# ESP32_LRThermostat_Relay_Driver_Board.net
KiCad netlist of a schematic drawn in EasyEDA
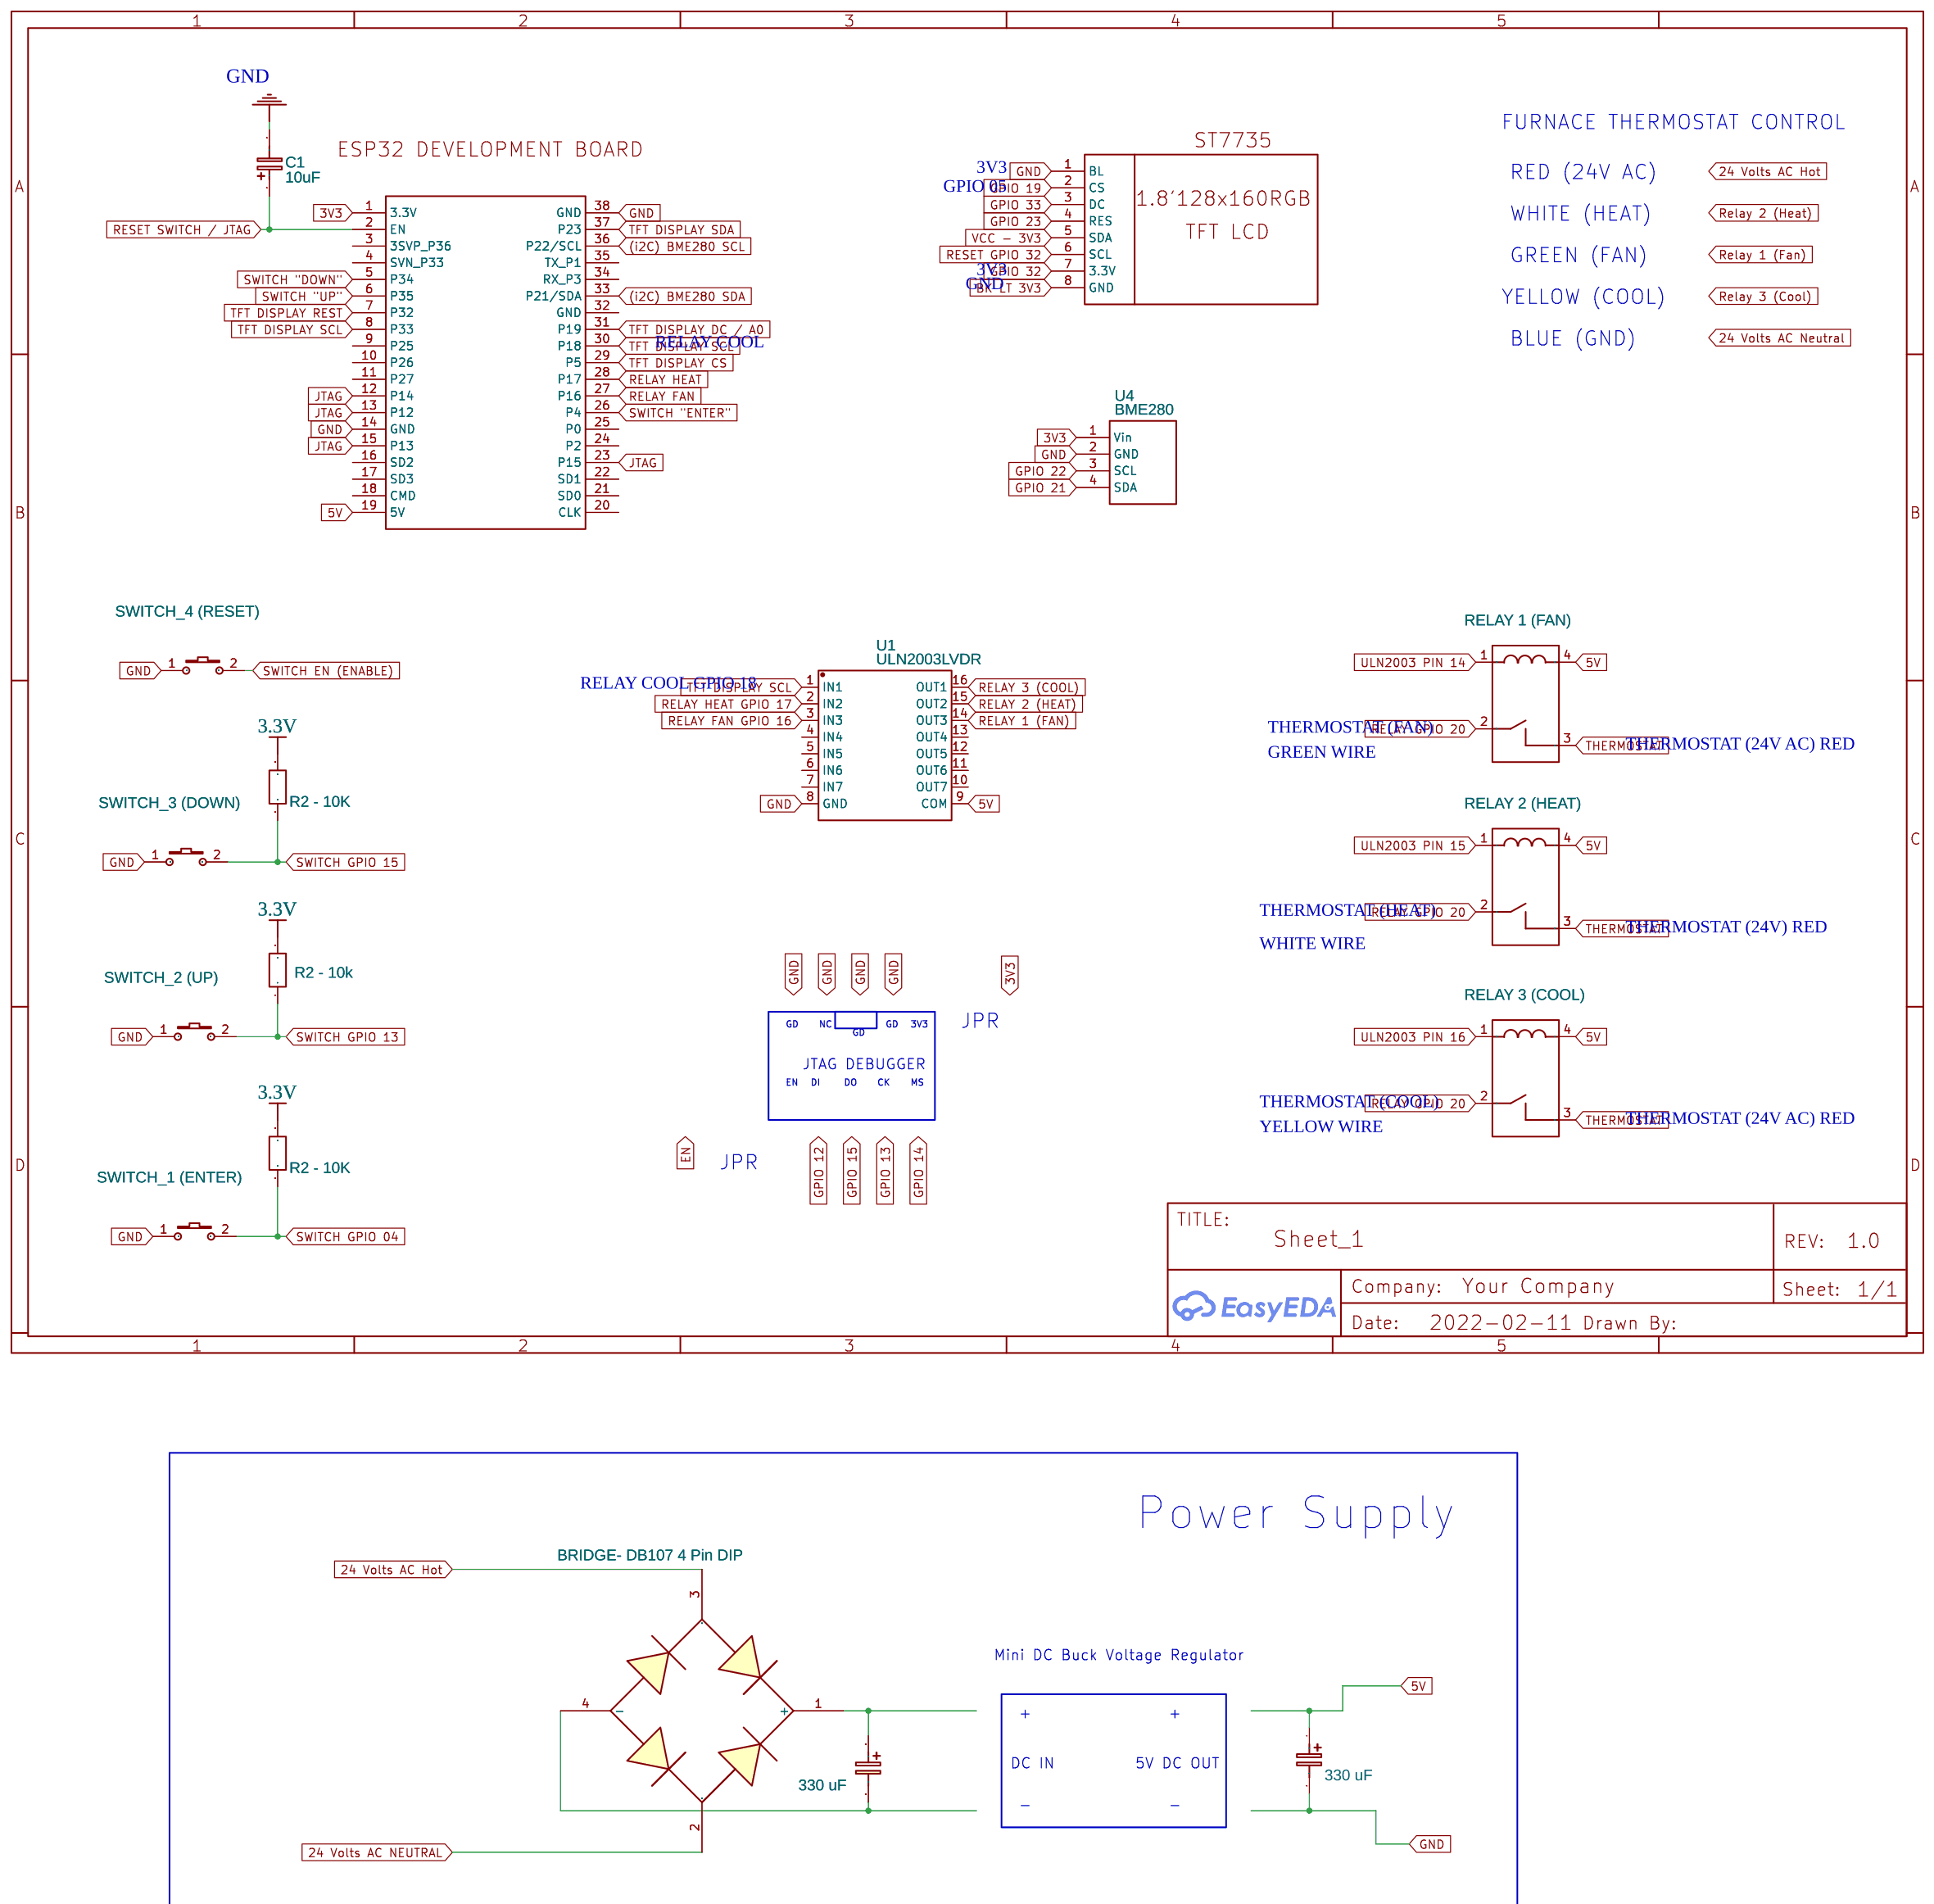
[diagram p0: schematic sheet]

(export (version "E")
  (design (tool "Eeschema 10.0.6"))
  (components
    (comp (ref "C1") (value "10uF") (libsource (lib "") (part "C_Tan_SMD_A_EU")))
    (comp (ref "C2") (value "330 uF") (libsource (lib "") (part "C_Tan_SMD_A_EU_1")))
    (comp (ref "C3") (value "330 uF") (libsource (lib "") (part "C_Tan_SMD_A_EU_1")))
    (comp (ref "D1") (value "BRIDGE- DB107 4 Pin DIP") (libsource (lib "") (part "BRIDGE-1")))
    (comp (ref "K1")
      (value "RELAY 2 (HEAT)")
      (fields
        (field (name "BOM_Manufacturer Part") "RJ-SS-112DM1-S")
        (field (name "BOM_Supplier Part") "C358580")
      )
      (libsource (lib "") (part "RJ-SS-112DM1-S"))
    )
    (comp (ref "K2")
      (value "RELAY 3 (COOL)")
      (fields
        (field (name "BOM_Manufacturer Part") "RJ-SS-112DM1-S")
        (field (name "BOM_Supplier Part") "C358580")
      )
      (libsource (lib "") (part "RJ-SS-112DM1-S"))
    )
    (comp (ref "K4")
      (value "RELAY 1 (FAN)")
      (fields
        (field (name "BOM_Manufacturer Part") "RJ-SS-112DM1-S")
        (field (name "BOM_Supplier Part") "C358580")
      )
      (libsource (lib "") (part "RJ-SS-112DM1-S"))
    )
    (comp (ref "KEY1")
      (value "SWITCH_4 (RESET)")
      (fields
        (field (name "BOM_Manufacturer Part") "K2-1107ST-A4SW-06")
        (field (name "BOM_Supplier Part") "C118141")
      )
      (libsource (lib "") (part "K2-3.6×6.1_SMD"))
    )
    (comp (ref "KEY4")
      (value "SWITCH_3 (DOWN)")
      (fields
        (field (name "BOM_Manufacturer Part") "K2-1107ST-A4SW-06")
        (field (name "BOM_Supplier Part") "C118141")
      )
      (libsource (lib "") (part "K2-3.6×6.1_SMD"))
    )
    (comp (ref "KEY5")
      (value "SWITCH_1 (ENTER)")
      (fields
        (field (name "BOM_Manufacturer Part") "K2-1107ST-A4SW-06")
        (field (name "BOM_Supplier Part") "C118141")
      )
      (libsource (lib "") (part "K2-3.6×6.1_SMD"))
    )
    (comp (ref "KEY6")
      (value "SWITCH_2 (UP)")
      (fields
        (field (name "BOM_Manufacturer Part") "K2-1107ST-A4SW-06")
        (field (name "BOM_Supplier Part") "C118141")
      )
      (libsource (lib "") (part "K2-3.6×6.1_SMD"))
    )
    (comp (ref "R1") (value "R2 - 10k") (libsource (lib "") (part "R_0603_EU")))
    (comp (ref "R2") (value "R2 - 10K") (libsource (lib "") (part "R_0603_EU")))
    (comp (ref "R3") (value "R2 - 10K") (libsource (lib "") (part "R_0603_EU")))
    (comp (ref "U1")
      (value "ULN2003LVDR")
      (fields (field (name "BOM_Supplier Part") "C72751"))
      (libsource (lib "") (part "ULN2003LVDR"))
    )
    (comp (ref "U2")
      (value "ESP32S Devkit")
      (fields (field (name "BOM_Manufacturer Part") "New SchematicLib"))
      (libsource (lib "") (part "ESP32S Devkit"))
    )
    (comp (ref "U3") (value "ST7735") (libsource (lib "") (part "ST7735")))
    (comp (ref "U4") (value "BME280") (libsource (lib "") (part "BME280")))
  )
  (nets
    (net (code "1") (name "(i2C) BME280 SCL") (class "Default")
      (node (ref "U2") (pin "36") (pinfunction "P22/SCL_36") (pintype "unspecified"))
    )
    (net (code "2") (name "(i2C) BME280 SDA") (class "Default")
      (node (ref "U2") (pin "33") (pinfunction "P21/SDA_33") (pintype "unspecified"))
    )
    (net (code "3") (name "3.3V") (class "Default")
      (node (ref "R1") (pin "2") (pinfunction "2_2") (pintype "unspecified"))
      (node (ref "R2") (pin "2") (pinfunction "2_2") (pintype "unspecified"))
      (node (ref "R3") (pin "2") (pinfunction "2_2") (pintype "unspecified"))
    )
    (net (code "4") (name "3V3") (class "Default")
      (node (ref "U2") (pin "1") (pinfunction "3.3V_1") (pintype "unspecified"))
      (node (ref "U4") (pin "1") (pinfunction "Vin_1") (pintype "unspecified"))
    )
    (net (code "5") (name "5V") (class "Default")
      (node (ref "C3") (pin "1") (pinfunction "1_1") (pintype "unspecified"))
      (node (ref "K1") (pin "4") (pinfunction "4_4") (pintype "unspecified"))
      (node (ref "K2") (pin "4") (pinfunction "4_4") (pintype "unspecified"))
      (node (ref "K4") (pin "4") (pinfunction "4_4") (pintype "unspecified"))
      (node (ref "U1") (pin "9") (pinfunction "COM_9") (pintype "unspecified"))
      (node (ref "U2") (pin "19") (pinfunction "5V_19") (pintype "unspecified"))
    )
    (net (code "6") (name "24 Volts AC Hot") (class "Default")
      (node (ref "D1") (pin "3") (pinfunction "3_3") (pintype "input"))
    )
    (net (code "7") (name "24 Volts AC NEUTRAL") (class "Default")
      (node (ref "D1") (pin "2") (pinfunction "2_2") (pintype "input"))
    )
    (net (code "9") (name "BK LT 3V3") (class "Default")
      (node (ref "U3") (pin "8") (pinfunction "GND_8") (pintype "unspecified"))
    )
    (net (code "11") (name "GND") (class "Default")
      (node (ref "C1") (pin "2") (pinfunction "2_2") (pintype "unspecified"))
      (node (ref "C3") (pin "2") (pinfunction "2_2") (pintype "unspecified"))
      (node (ref "KEY1") (pin "1") (pinfunction "1_1") (pintype "unspecified"))
      (node (ref "KEY4") (pin "1") (pinfunction "1_1") (pintype "unspecified"))
      (node (ref "KEY5") (pin "1") (pinfunction "1_1") (pintype "unspecified"))
      (node (ref "KEY6") (pin "1") (pinfunction "1_1") (pintype "unspecified"))
      (node (ref "U1") (pin "8") (pinfunction "GND_8") (pintype "unspecified"))
      (node (ref "U2") (pin "14") (pinfunction "GND_14") (pintype "unspecified"))
      (node (ref "U2") (pin "38") (pinfunction "GND_38") (pintype "unspecified"))
      (node (ref "U3") (pin "1") (pinfunction "BL_1") (pintype "unspecified"))
      (node (ref "U4") (pin "2") (pinfunction "GND_2") (pintype "unspecified"))
    )
    (net (code "16") (name "GPIO 19") (class "Default")
      (node (ref "U3") (pin "2") (pinfunction "CS_2") (pintype "unspecified"))
    )
    (net (code "17") (name "GPIO 21") (class "Default")
      (node (ref "U4") (pin "4") (pinfunction "SDA_4") (pintype "unspecified"))
    )
    (net (code "18") (name "GPIO 22") (class "Default")
      (node (ref "U4") (pin "3") (pinfunction "SCL_3") (pintype "unspecified"))
    )
    (net (code "19") (name "GPIO 23") (class "Default")
      (node (ref "U3") (pin "4") (pinfunction "RES_4") (pintype "unspecified"))
    )
    (net (code "20") (name "GPIO 32") (class "Default")
      (node (ref "U3") (pin "7") (pinfunction "3.3V_7") (pintype "unspecified"))
    )
    (net (code "21") (name "GPIO 33") (class "Default")
      (node (ref "U3") (pin "3") (pinfunction "DC_3") (pintype "unspecified"))
    )
    (net (code "22") (name "JTAG") (class "Default")
      (node (ref "U2") (pin "12") (pinfunction "P14_12") (pintype "unspecified"))
      (node (ref "U2") (pin "13") (pinfunction "P12_13") (pintype "unspecified"))
      (node (ref "U2") (pin "15") (pinfunction "P13_15") (pintype "unspecified"))
      (node (ref "U2") (pin "23") (pinfunction "P15_23") (pintype "unspecified"))
    )
    (net (code "23") (name "Net-(D1-+)") (class "Default")
      (node (ref "C2") (pin "1") (pinfunction "1_1") (pintype "unspecified"))
      (node (ref "D1") (pin "1") (pinfunction "+_1") (pintype "input"))
    )
    (net (code "24") (name "Net-(D1--)") (class "Default")
      (node (ref "C2") (pin "2") (pinfunction "2_2") (pintype "unspecified"))
      (node (ref "D1") (pin "4") (pinfunction "-_4") (pintype "input"))
    )
    (net (code "25") (name "RELAY 1 (FAN)") (class "Default")
      (node (ref "U1") (pin "14") (pinfunction "OUT3_14") (pintype "unspecified"))
    )
    (net (code "26") (name "RELAY 2 (HEAT)") (class "Default")
      (node (ref "U1") (pin "15") (pinfunction "OUT2_15") (pintype "unspecified"))
    )
    (net (code "27") (name "RELAY 3 (COOL)") (class "Default")
      (node (ref "U1") (pin "16") (pinfunction "OUT1_16") (pintype "unspecified"))
    )
    (net (code "28") (name "RELAY FAN") (class "Default")
      (node (ref "U2") (pin "27") (pinfunction "P16_27") (pintype "unspecified"))
    )
    (net (code "29") (name "RELAY FAN GPIO 16") (class "Default")
      (node (ref "U1") (pin "3") (pinfunction "IN3_3") (pintype "unspecified"))
    )
    (net (code "30") (name "RELAY GPIO 20") (class "Default")
      (node (ref "K1") (pin "2") (pinfunction "2_2") (pintype "unspecified"))
      (node (ref "K2") (pin "2") (pinfunction "2_2") (pintype "unspecified"))
      (node (ref "K4") (pin "2") (pinfunction "2_2") (pintype "unspecified"))
    )
    (net (code "31") (name "RELAY HEAT") (class "Default")
      (node (ref "U2") (pin "28") (pinfunction "P17_28") (pintype "unspecified"))
    )
    (net (code "32") (name "RELAY HEAT GPIO 17") (class "Default")
      (node (ref "U1") (pin "2") (pinfunction "IN2_2") (pintype "unspecified"))
    )
    (net (code "33") (name "RESET GPIO 32") (class "Default")
      (node (ref "U3") (pin "6") (pinfunction "SCL_6") (pintype "unspecified"))
    )
    (net (code "34") (name "RESET SWITCH {slash} JTAG") (class "Default")
      (node (ref "C1") (pin "1") (pinfunction "1_1") (pintype "unspecified"))
      (node (ref "U2") (pin "2") (pinfunction "EN_2") (pintype "unspecified"))
    )
    (net (code "38") (name "SWITCH \"DOWN\"") (class "Default")
      (node (ref "U2") (pin "5") (pinfunction "P34_5") (pintype "unspecified"))
    )
    (net (code "39") (name "SWITCH \"ENTER\"") (class "Default")
      (node (ref "U2") (pin "26") (pinfunction "P4_26") (pintype "unspecified"))
    )
    (net (code "40") (name "SWITCH \"UP\"") (class "Default")
      (node (ref "U2") (pin "6") (pinfunction "P35_6") (pintype "unspecified"))
    )
    (net (code "41") (name "SWITCH EN (ENABLE)") (class "Default")
      (node (ref "KEY1") (pin "2") (pinfunction "2_2") (pintype "unspecified"))
    )
    (net (code "42") (name "SWITCH GPIO 04") (class "Default")
      (node (ref "KEY5") (pin "2") (pinfunction "2_2") (pintype "unspecified"))
      (node (ref "R2") (pin "1") (pinfunction "1_1") (pintype "unspecified"))
    )
    (net (code "43") (name "SWITCH GPIO 13") (class "Default")
      (node (ref "KEY6") (pin "2") (pinfunction "2_2") (pintype "unspecified"))
      (node (ref "R1") (pin "1") (pinfunction "1_1") (pintype "unspecified"))
    )
    (net (code "44") (name "SWITCH GPIO 15") (class "Default")
      (node (ref "KEY4") (pin "2") (pinfunction "2_2") (pintype "unspecified"))
      (node (ref "R3") (pin "1") (pinfunction "1_1") (pintype "unspecified"))
    )
    (net (code "45") (name "TFT DISPLAY CS") (class "Default")
      (node (ref "U2") (pin "29") (pinfunction "P5_29") (pintype "unspecified"))
    )
    (net (code "46") (name "TFT DISPLAY DC {slash} A0") (class "Default")
      (node (ref "U2") (pin "31") (pinfunction "P19_31") (pintype "unspecified"))
    )
    (net (code "47") (name "TFT DISPLAY REST") (class "Default")
      (node (ref "U2") (pin "7") (pinfunction "P32_7") (pintype "unspecified"))
    )
    (net (code "48") (name "TFT DISPLAY SCL") (class "Default")
      (node (ref "U1") (pin "1") (pinfunction "IN1_1") (pintype "unspecified"))
      (node (ref "U2") (pin "30") (pinfunction "P18_30") (pintype "unspecified"))
      (node (ref "U2") (pin "8") (pinfunction "P33_8") (pintype "unspecified"))
    )
    (net (code "49") (name "TFT DISPLAY SDA") (class "Default")
      (node (ref "U2") (pin "37") (pinfunction "P23_37") (pintype "unspecified"))
    )
    (net (code "50") (name "THERMOSTAT") (class "Default")
      (node (ref "K1") (pin "3") (pinfunction "3_3") (pintype "unspecified"))
      (node (ref "K2") (pin "3") (pinfunction "3_3") (pintype "unspecified"))
      (node (ref "K4") (pin "3") (pinfunction "3_3") (pintype "unspecified"))
    )
    (net (code "51") (name "ULN2003 PIN 14") (class "Default")
      (node (ref "K4") (pin "1") (pinfunction "1_1") (pintype "unspecified"))
    )
    (net (code "52") (name "ULN2003 PIN 15") (class "Default")
      (node (ref "K1") (pin "1") (pinfunction "1_1") (pintype "unspecified"))
    )
    (net (code "53") (name "ULN2003 PIN 16") (class "Default")
      (node (ref "K2") (pin "1") (pinfunction "1_1") (pintype "unspecified"))
    )
    (net (code "54") (name "VCC - 3V3") (class "Default")
      (node (ref "U3") (pin "5") (pinfunction "SDA_5") (pintype "unspecified"))
    )
    (net (code "55") (name "unconnected-(U1-IN4-Pad4)") (class "Default")
      (node (ref "U1") (pin "4") (pinfunction "IN4_4") (pintype "unspecified"))
    )
    (net (code "56") (name "unconnected-(U1-IN5-Pad5)") (class "Default")
      (node (ref "U1") (pin "5") (pinfunction "IN5_5") (pintype "unspecified"))
    )
    (net (code "57") (name "unconnected-(U1-IN6-Pad6)") (class "Default")
      (node (ref "U1") (pin "6") (pinfunction "IN6_6") (pintype "unspecified"))
    )
    (net (code "58") (name "unconnected-(U1-IN7-Pad7)") (class "Default")
      (node (ref "U1") (pin "7") (pinfunction "IN7_7") (pintype "unspecified"))
    )
    (net (code "59") (name "unconnected-(U1-OUT4-Pad13)") (class "Default")
      (node (ref "U1") (pin "13") (pinfunction "OUT4_13") (pintype "unspecified"))
    )
    (net (code "60") (name "unconnected-(U1-OUT5-Pad12)") (class "Default")
      (node (ref "U1") (pin "12") (pinfunction "OUT5_12") (pintype "unspecified"))
    )
    (net (code "61") (name "unconnected-(U1-OUT6-Pad11)") (class "Default")
      (node (ref "U1") (pin "11") (pinfunction "OUT6_11") (pintype "unspecified"))
    )
    (net (code "62") (name "unconnected-(U1-OUT7-Pad10)") (class "Default")
      (node (ref "U1") (pin "10") (pinfunction "OUT7_10") (pintype "unspecified"))
    )
    (net (code "63") (name "unconnected-(U2-3SVP_P36-Pad3)") (class "Default")
      (node (ref "U2") (pin "3") (pinfunction "3SVP_P36_3") (pintype "unspecified"))
    )
    (net (code "64") (name "unconnected-(U2-CLK-Pad20)") (class "Default")
      (node (ref "U2") (pin "20") (pinfunction "CLK_20") (pintype "unspecified"))
    )
    (net (code "65") (name "unconnected-(U2-CMD-Pad18)") (class "Default")
      (node (ref "U2") (pin "18") (pinfunction "CMD_18") (pintype "unspecified"))
    )
    (net (code "66") (name "unconnected-(U2-GND-Pad32)") (class "Default")
      (node (ref "U2") (pin "32") (pinfunction "GND_32") (pintype "unspecified"))
    )
    (net (code "67") (name "unconnected-(U2-P0-Pad25)") (class "Default")
      (node (ref "U2") (pin "25") (pinfunction "P0_25") (pintype "unspecified"))
    )
    (net (code "68") (name "unconnected-(U2-P2-Pad24)") (class "Default")
      (node (ref "U2") (pin "24") (pinfunction "P2_24") (pintype "unspecified"))
    )
    (net (code "69") (name "unconnected-(U2-P25-Pad9)") (class "Default")
      (node (ref "U2") (pin "9") (pinfunction "P25_9") (pintype "unspecified"))
    )
    (net (code "70") (name "unconnected-(U2-P26-Pad10)") (class "Default")
      (node (ref "U2") (pin "10") (pinfunction "P26_10") (pintype "unspecified"))
    )
    (net (code "71") (name "unconnected-(U2-P27-Pad11)") (class "Default")
      (node (ref "U2") (pin "11") (pinfunction "P27_11") (pintype "unspecified"))
    )
    (net (code "72") (name "unconnected-(U2-RX_P3-Pad34)") (class "Default")
      (node (ref "U2") (pin "34") (pinfunction "RX_P3_34") (pintype "unspecified"))
    )
    (net (code "73") (name "unconnected-(U2-SD0-Pad21)") (class "Default")
      (node (ref "U2") (pin "21") (pinfunction "SD0_21") (pintype "unspecified"))
    )
    (net (code "74") (name "unconnected-(U2-SD1-Pad22)") (class "Default")
      (node (ref "U2") (pin "22") (pinfunction "SD1_22") (pintype "unspecified"))
    )
    (net (code "75") (name "unconnected-(U2-SD2-Pad16)") (class "Default")
      (node (ref "U2") (pin "16") (pinfunction "SD2_16") (pintype "unspecified"))
    )
    (net (code "76") (name "unconnected-(U2-SD3-Pad17)") (class "Default")
      (node (ref "U2") (pin "17") (pinfunction "SD3_17") (pintype "unspecified"))
    )
    (net (code "77") (name "unconnected-(U2-SVN_P33-Pad4)") (class "Default")
      (node (ref "U2") (pin "4") (pinfunction "SVN_P33_4") (pintype "unspecified"))
    )
    (net (code "78") (name "unconnected-(U2-TX_P1-Pad35)") (class "Default")
      (node (ref "U2") (pin "35") (pinfunction "TX_P1_35") (pintype "unspecified"))
    )
  )
)
